# Top.net
KiCad netlist of a schematic drawn in Altium Designer
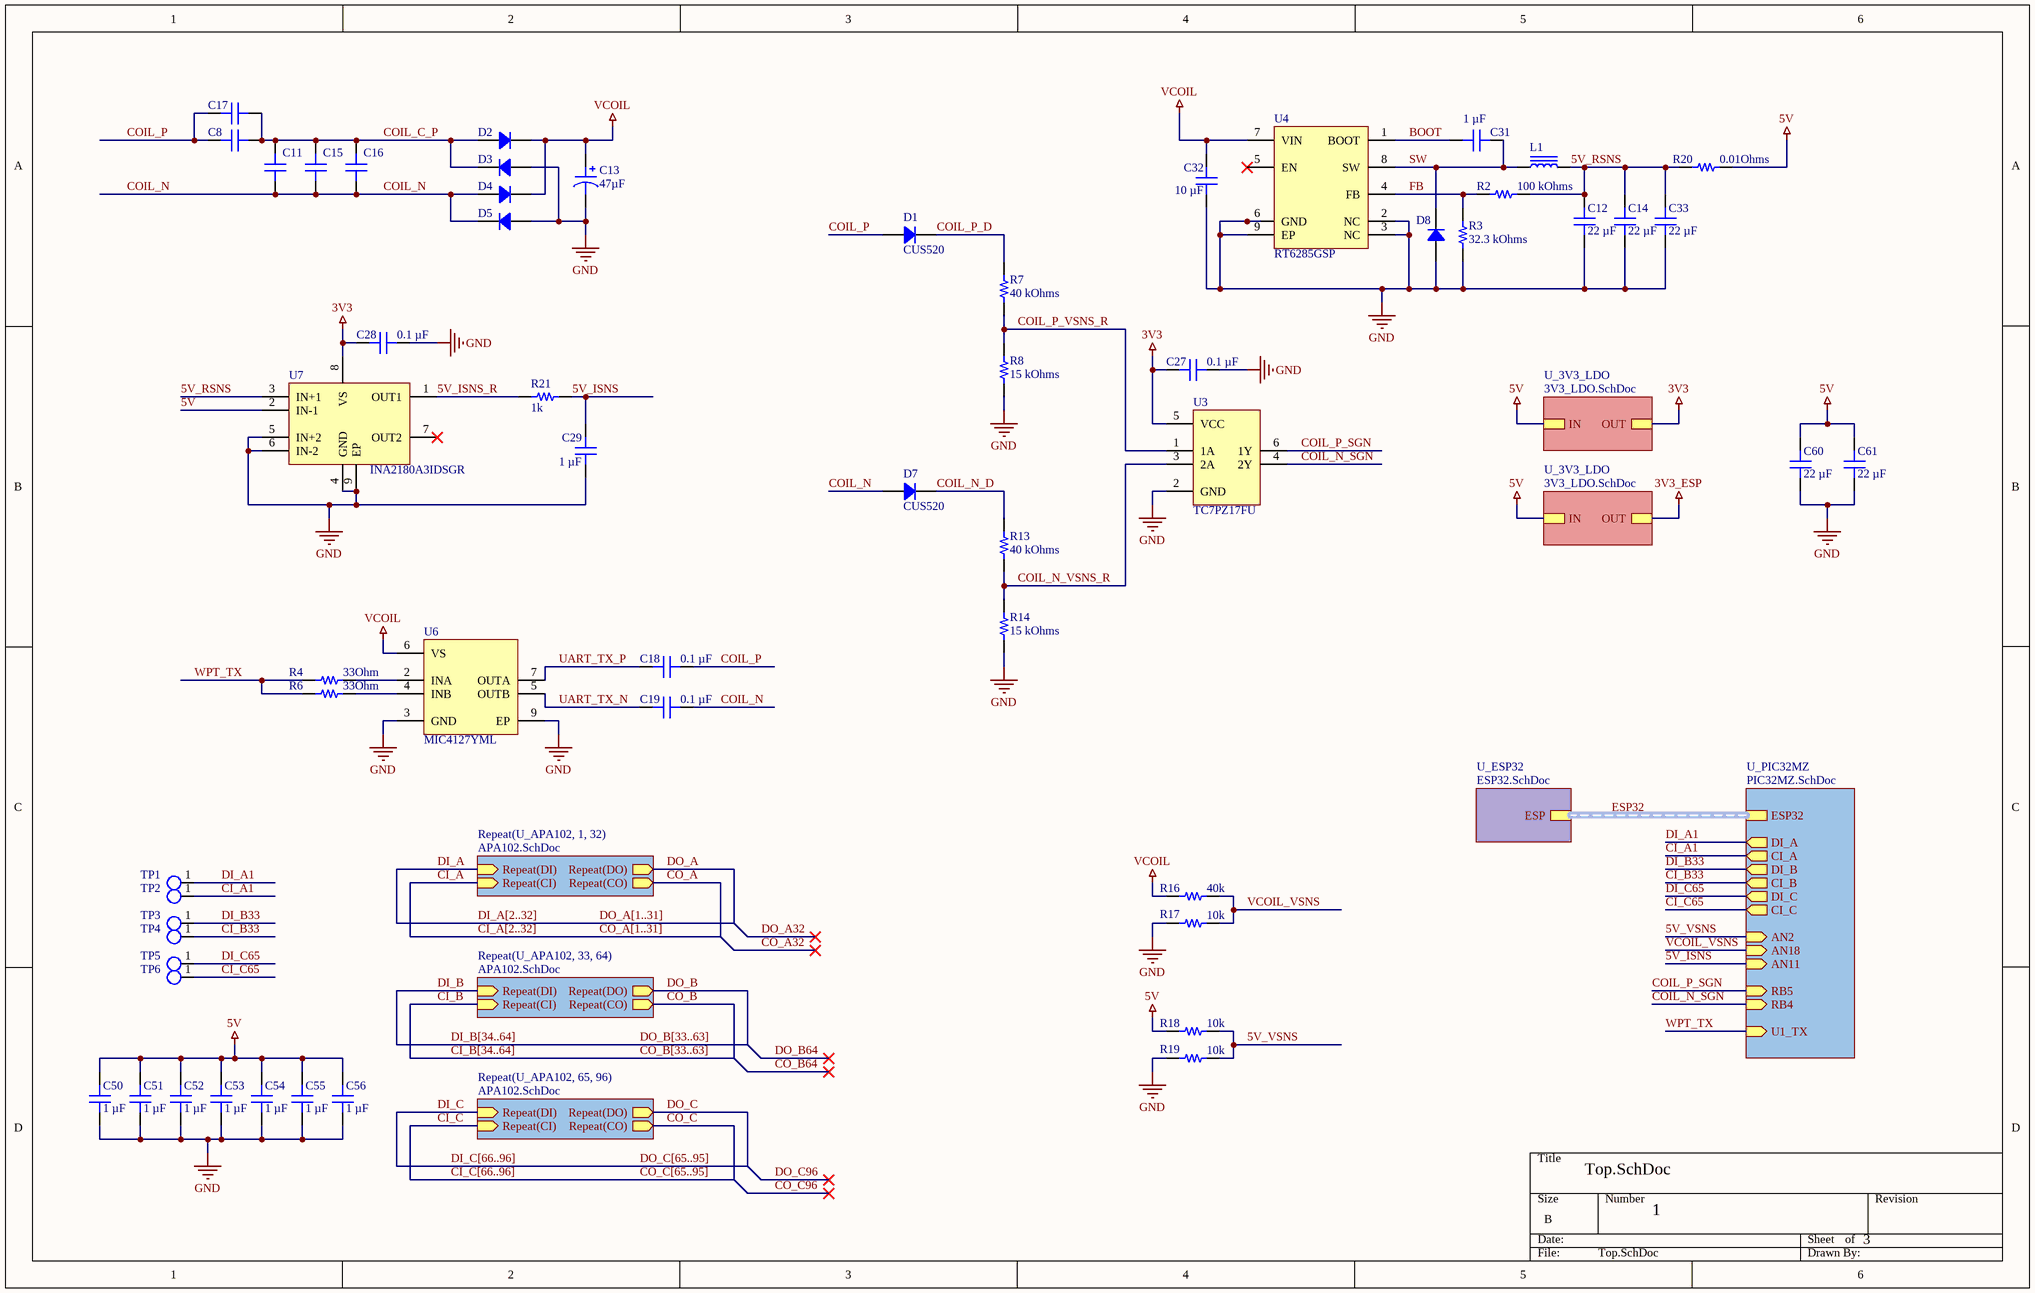
[diagram p0: Top.SchDoc]

(export (version "E")
  (design (tool "Eeschema 10.0.6"))
  (components
    (comp (ref "C8")
      (value "~")
      (footprint "CAP 1206_3216 - 0.8MM")
      (description "CAP CER 0.022UF 630V X7R 1206")
      (fields (field (name "PART NUMBER") "C1206C223KBRAC7800") (field (name "MANUFACTURER") "KEMET"))
      (libsource (lib "Celestial Altium Library - altium_library") (part "Capacitor"))
    )
    (comp (ref "C11")
      (value "~")
      (footprint "CAP 1206_3216 - 0.8MM")
      (description "CAP CER 0.022UF 630V X7R 1206")
      (fields (field (name "PART NUMBER") "C1206C223KBRAC7800") (field (name "MANUFACTURER") "KEMET"))
      (libsource (lib "Celestial Altium Library - altium_library") (part "Capacitor"))
    )
    (comp (ref "C12")
      (value "22 µF")
      (footprint "CAP 0603_1608")
      (description "CAP CER 22UF 10V X5R 0603")
      (fields (field (name "PART NUMBER") "0603ZD226MAT2A") (field (name "MANUFACTURER") "KYOCERA AVX"))
      (libsource (lib "Celestial Altium Library - altium_library") (part "Capacitor"))
    )
    (comp (ref "C13")
      (value "47µF")
      (footprint "CAP ALSMD 6.6MM H6.1MM")
      (description "ALUMINUM CAPACITOR")
      (fields
        (field (name "PART NUMBER") "EMHL160ARA470MF61G")
        (field (name "MANUFACTURER") "United Chemi-Con")
      )
      (libsource (lib "Celestial Altium Library - altium_library") (part "Polarised Capacitor"))
    )
    (comp (ref "C14")
      (value "22 µF")
      (footprint "CAP 0603_1608")
      (description "CAP CER 22UF 10V X5R 0603")
      (fields (field (name "PART NUMBER") "0603ZD226MAT2A") (field (name "MANUFACTURER") "KYOCERA AVX"))
      (libsource (lib "Celestial Altium Library - altium_library") (part "Capacitor"))
    )
    (comp (ref "C15")
      (value "~")
      (footprint "CAP 1206_3216 - 0.8MM")
      (description "CAP CER 0.022UF 630V X7R 1206")
      (fields (field (name "PART NUMBER") "C1206C223KBRAC7800") (field (name "MANUFACTURER") "KEMET"))
      (libsource (lib "Celestial Altium Library - altium_library") (part "Capacitor"))
    )
    (comp (ref "C16")
      (value "~")
      (footprint "CAP 1206_3216 - 0.8MM")
      (description "CAP CER 0.022UF 630V X7R 1206")
      (fields (field (name "PART NUMBER") "C1206C223KBRAC7800") (field (name "MANUFACTURER") "KEMET"))
      (libsource (lib "Celestial Altium Library - altium_library") (part "Capacitor"))
    )
    (comp (ref "C17")
      (value "~")
      (footprint "CAP 1206_3216 - 0.8MM")
      (description "CAP CER 0.022UF 630V X7R 1206")
      (fields (field (name "PART NUMBER") "C1206C223KBRAC7800") (field (name "MANUFACTURER") "KEMET"))
      (libsource (lib "Celestial Altium Library - altium_library") (part "Capacitor"))
    )
    (comp (ref "C18")
      (value "0.1 µF")
      (footprint "CAP 0402_1005")
      (description "CAP CER 0.1UF 25V X5R 0402")
      (fields
        (field (name "PART NUMBER") "C1005X5R1E104K050BC")
        (field (name "MANUFACTURER") "TDK Corporation")
      )
      (libsource (lib "Celestial Altium Library - altium_library") (part "Capacitor"))
    )
    (comp (ref "C19")
      (value "0.1 µF")
      (footprint "CAP 0402_1005")
      (description "CAP CER 0.1UF 25V X5R 0402")
      (fields
        (field (name "PART NUMBER") "C1005X5R1E104K050BC")
        (field (name "MANUFACTURER") "TDK Corporation")
      )
      (libsource (lib "Celestial Altium Library - altium_library") (part "Capacitor"))
    )
    (comp (ref "C27")
      (value "0.1 µF")
      (footprint "CAP 0402_1005")
      (description "CAP CER 0.1UF 25V X5R 0402")
      (fields
        (field (name "PART NUMBER") "C1005X5R1E104K050BC")
        (field (name "MANUFACTURER") "TDK Corporation")
      )
      (libsource (lib "Celestial Altium Library - altium_library") (part "Capacitor"))
    )
    (comp (ref "C28")
      (value "0.1 µF")
      (footprint "CAP 0402_1005")
      (description "CAP CER 0.1UF 25V X5R 0402")
      (fields
        (field (name "PART NUMBER") "C1005X5R1E104K050BC")
        (field (name "MANUFACTURER") "TDK Corporation")
      )
      (libsource (lib "Celestial Altium Library - altium_library") (part "Capacitor"))
    )
    (comp (ref "C29")
      (value "1 µF")
      (footprint "CAP 0402_1005")
      (description "CAP CER 0.1UF 25V X5R 0402")
      (fields
        (field (name "PART NUMBER") "C1005X5R1E104K050BC")
        (field (name "MANUFACTURER") "TDK Corporation")
      )
      (libsource (lib "Celestial Altium Library - altium_library") (part "Capacitor"))
    )
    (comp (ref "C31")
      (value "1 µF")
      (footprint "CAP 0402_1005")
      (description "CAP CER 0.1UF 25V X5R 0402")
      (fields
        (field (name "PART NUMBER") "C1005X5R1E104K050BC")
        (field (name "MANUFACTURER") "TDK Corporation")
      )
      (libsource (lib "Celestial Altium Library - altium_library") (part "Capacitor"))
    )
    (comp (ref "C32")
      (value "10 µF")
      (footprint "CAP 1210_3225 - 1MM")
      (description "CAP CER 10UF 50V X7R 1210")
      (fields
        (field (name "PART NUMBER") "C1210X106K050T")
        (field (name "MANUFACTURER") "Holy Stone Enterprise Co., Ltd.")
      )
      (libsource (lib "Celestial Altium Library - altium_library") (part "Capacitor"))
    )
    (comp (ref "C33")
      (value "22 µF")
      (footprint "CAP 0603_1608")
      (description "CAP CER 22UF 10V X5R 0603")
      (fields (field (name "PART NUMBER") "0603ZD226MAT2A") (field (name "MANUFACTURER") "KYOCERA AVX"))
      (libsource (lib "Celestial Altium Library - altium_library") (part "Capacitor"))
    )
    (comp (ref "C50")
      (value "1 µF")
      (footprint "CAP 0402_1005")
      (description "CAP CER 1UF 16V X5R 0402")
      (fields
        (field (name "PART NUMBER") "GRM155R61C105MA12D")
        (field (name "MANUFACTURER") "Murata Electronics")
      )
      (libsource (lib "Celestial Altium Library - altium_library") (part "Capacitor"))
    )
    (comp (ref "C51")
      (value "1 µF")
      (footprint "CAP 0402_1005")
      (description "CAP CER 1UF 16V X5R 0402")
      (fields
        (field (name "PART NUMBER") "GRM155R61C105MA12D")
        (field (name "MANUFACTURER") "Murata Electronics")
      )
      (libsource (lib "Celestial Altium Library - altium_library") (part "Capacitor"))
    )
    (comp (ref "C52")
      (value "1 µF")
      (footprint "CAP 0402_1005")
      (description "CAP CER 1UF 16V X5R 0402")
      (fields
        (field (name "PART NUMBER") "GRM155R61C105MA12D")
        (field (name "MANUFACTURER") "Murata Electronics")
      )
      (libsource (lib "Celestial Altium Library - altium_library") (part "Capacitor"))
    )
    (comp (ref "C53")
      (value "1 µF")
      (footprint "CAP 0402_1005")
      (description "CAP CER 1UF 16V X5R 0402")
      (fields
        (field (name "PART NUMBER") "GRM155R61C105MA12D")
        (field (name "MANUFACTURER") "Murata Electronics")
      )
      (libsource (lib "Celestial Altium Library - altium_library") (part "Capacitor"))
    )
    (comp (ref "C54")
      (value "1 µF")
      (footprint "CAP 0402_1005")
      (description "CAP CER 1UF 16V X5R 0402")
      (fields
        (field (name "PART NUMBER") "GRM155R61C105MA12D")
        (field (name "MANUFACTURER") "Murata Electronics")
      )
      (libsource (lib "Celestial Altium Library - altium_library") (part "Capacitor"))
    )
    (comp (ref "C55")
      (value "1 µF")
      (footprint "CAP 0402_1005")
      (description "CAP CER 1UF 16V X5R 0402")
      (fields
        (field (name "PART NUMBER") "GRM155R61C105MA12D")
        (field (name "MANUFACTURER") "Murata Electronics")
      )
      (libsource (lib "Celestial Altium Library - altium_library") (part "Capacitor"))
    )
    (comp (ref "C56")
      (value "1 µF")
      (footprint "CAP 0402_1005")
      (description "CAP CER 1UF 16V X5R 0402")
      (fields
        (field (name "PART NUMBER") "GRM155R61C105MA12D")
        (field (name "MANUFACTURER") "Murata Electronics")
      )
      (libsource (lib "Celestial Altium Library - altium_library") (part "Capacitor"))
    )
    (comp (ref "C60")
      (value "22 µF")
      (footprint "CAP 0603_1608")
      (description "CAP CER 22UF 10V X5R 0603")
      (fields (field (name "PART NUMBER") "0603ZD226MAT2A") (field (name "MANUFACTURER") "KYOCERA AVX"))
      (libsource (lib "Celestial Altium Library - altium_library") (part "Capacitor"))
    )
    (comp (ref "C61")
      (value "22 µF")
      (footprint "CAP 0603_1608")
      (description "CAP CER 22UF 10V X5R 0603")
      (fields (field (name "PART NUMBER") "0603ZD226MAT2A") (field (name "MANUFACTURER") "KYOCERA AVX"))
      (libsource (lib "Celestial Altium Library - altium_library") (part "Capacitor"))
    )
    (comp (ref "D1")
      (value "CUS520")
      (footprint "SOD323")
      (description "DIODE SCHOTTKY 30V 30MA SOD323")
      (fields (field (name "PART NUMBER") "NSVRB751V40T1G") (field (name "MANUFACTURER") "ON Semiconductor"))
      (libsource (lib "Celestial Altium Library - altium_library") (part "Diode"))
    )
    (comp (ref "D2")
      (value "STPS340UY")
      (footprint "DO214AA SMB")
      (description "DIODE SCHOTTKY 40V 3A SMB")
      (fields (field (name "MANUFACTURER") "STMicroelectronics"))
      (libsource (lib "Celestial Altium Library - altium_library") (part "Diode"))
    )
    (comp (ref "D3")
      (value "STPS340UY")
      (footprint "DO214AA SMB")
      (description "DIODE SCHOTTKY 40V 3A SMB")
      (fields (field (name "MANUFACTURER") "STMicroelectronics"))
      (libsource (lib "Celestial Altium Library - altium_library") (part "Diode"))
    )
    (comp (ref "D4")
      (value "STPS340UY")
      (footprint "DO214AA SMB")
      (description "DIODE SCHOTTKY 40V 3A SMB")
      (fields (field (name "MANUFACTURER") "STMicroelectronics"))
      (libsource (lib "Celestial Altium Library - altium_library") (part "Diode"))
    )
    (comp (ref "D5")
      (value "STPS340UY")
      (footprint "DO214AA SMB")
      (description "DIODE SCHOTTKY 40V 3A SMB")
      (fields (field (name "MANUFACTURER") "STMicroelectronics"))
      (libsource (lib "Celestial Altium Library - altium_library") (part "Diode"))
    )
    (comp (ref "D7")
      (value "CUS520")
      (footprint "SOD323")
      (description "DIODE SCHOTTKY 30V 30MA SOD323")
      (fields (field (name "PART NUMBER") "NSVRB751V40T1G") (field (name "MANUFACTURER") "ON Semiconductor"))
      (libsource (lib "Celestial Altium Library - altium_library") (part "Diode"))
    )
    (comp (ref "D8")
      (value "STPS340UY")
      (footprint "DO214AA SMB")
      (description "DIODE SCHOTTKY 40V 3A SMB")
      (fields (field (name "MANUFACTURER") "STMicroelectronics"))
      (libsource (lib "Celestial Altium Library - altium_library") (part "Diode"))
    )
    (comp (ref "L1")
      (value "MPL-AL5050-5R6")
      (footprint "MPL-AL5050-5R6")
      (description "FIXED IND 5.6UH 6.8A 20 MOHM SMD")
      (fields (field (name "MF") "Laird-Signal Integrity Products") (field (name "MP") "MGV05021R0M-10"))
      (libsource (lib "IC") (part "MPL-AL5050-5R6"))
    )
    (comp (ref "R2")
      (value "100 kOhms")
      (footprint "RES 0402_1005")
      (description "RES SMD 220K OHM 5% 1/5W 0402")
      (fields (field (name "PART NUMBER") "ESR01MZPJ224") (field (name "MANUFACTURER") "Rohm Semiconductor"))
      (libsource (lib "Celestial Altium Library - altium_library") (part "Resistor"))
    )
    (comp (ref "R3")
      (value "32.3 kOhms")
      (footprint "RES 0402_1005")
      (description "RES SMD 30K OHM 0.5% 1/16W 0402")
      (fields (field (name "PART NUMBER") "RT0402DRE0730KL") (field (name "MANUFACTURER") "Yageo"))
      (libsource (lib "Celestial Altium Library - altium_library") (part "Resistor"))
    )
    (comp (ref "R4")
      (value "33Ohm")
      (footprint "RES 0402_1005")
      (description "RES SMD 220K OHM 5% 1/5W 0402")
      (fields (field (name "PART NUMBER") "ESR01MZPJ224") (field (name "MANUFACTURER") "Rohm Semiconductor"))
      (libsource (lib "Celestial Altium Library - altium_library") (part "Resistor"))
    )
    (comp (ref "R6")
      (value "33Ohm")
      (footprint "RES 0402_1005")
      (description "RES SMD 220K OHM 5% 1/5W 0402")
      (fields (field (name "PART NUMBER") "ESR01MZPJ224") (field (name "MANUFACTURER") "Rohm Semiconductor"))
      (libsource (lib "Celestial Altium Library - altium_library") (part "Resistor"))
    )
    (comp (ref "R7")
      (value "40 kOhms")
      (footprint "RES 0402_1005")
      (description "RES SMD 30K OHM 0.5% 1/16W 0402")
      (fields (field (name "PART NUMBER") "RT0402DRE0730KL") (field (name "MANUFACTURER") "Yageo"))
      (libsource (lib "Celestial Altium Library - altium_library") (part "Resistor"))
    )
    (comp (ref "R8")
      (value "15 kOhms")
      (footprint "RES 0402_1005")
      (description "RES SMD 30K OHM 0.5% 1/16W 0402")
      (fields (field (name "PART NUMBER") "RT0402DRE0730KL") (field (name "MANUFACTURER") "Yageo"))
      (libsource (lib "Celestial Altium Library - altium_library") (part "Resistor"))
    )
    (comp (ref "R13")
      (value "40 kOhms")
      (footprint "RES 0402_1005")
      (description "RES SMD 30K OHM 0.5% 1/16W 0402")
      (fields (field (name "PART NUMBER") "RT0402DRE0730KL") (field (name "MANUFACTURER") "Yageo"))
      (libsource (lib "Celestial Altium Library - altium_library") (part "Resistor"))
    )
    (comp (ref "R14")
      (value "15 kOhms")
      (footprint "RES 0402_1005")
      (description "RES SMD 30K OHM 0.5% 1/16W 0402")
      (fields (field (name "PART NUMBER") "RT0402DRE0730KL") (field (name "MANUFACTURER") "Yageo"))
      (libsource (lib "Celestial Altium Library - altium_library") (part "Resistor"))
    )
    (comp (ref "R16")
      (value "40k")
      (footprint "RES 0402_1005")
      (description "RES SMD 30K OHM 0.5% 1/16W 0402")
      (fields (field (name "PART NUMBER") "RT0402DRE0730KL") (field (name "MANUFACTURER") "Yageo"))
      (libsource (lib "Celestial Altium Library - altium_library") (part "Resistor"))
    )
    (comp (ref "R17")
      (value "10k")
      (footprint "RES 0402_1005")
      (description "RES SMD 30K OHM 0.5% 1/16W 0402")
      (fields (field (name "PART NUMBER") "RT0402DRE0730KL") (field (name "MANUFACTURER") "Yageo"))
      (libsource (lib "Celestial Altium Library - altium_library") (part "Resistor"))
    )
    (comp (ref "R18")
      (value "10k")
      (footprint "RES 0402_1005")
      (description "RES SMD 30K OHM 0.5% 1/16W 0402")
      (fields (field (name "PART NUMBER") "RT0402DRE0730KL") (field (name "MANUFACTURER") "Yageo"))
      (libsource (lib "Celestial Altium Library - altium_library") (part "Resistor"))
    )
    (comp (ref "R19")
      (value "10k")
      (footprint "RES 0402_1005")
      (description "RES SMD 30K OHM 0.5% 1/16W 0402")
      (fields (field (name "PART NUMBER") "RT0402DRE0730KL") (field (name "MANUFACTURER") "Yageo"))
      (libsource (lib "Celestial Altium Library - altium_library") (part "Resistor"))
    )
    (comp (ref "R20")
      (value "0.01Ohms")
      (footprint "RES 0805_2012")
      (description "0805 CURRENT SENSING RES. 0.5%,")
      (fields
        (field (name "PART NUMBER") "ERJ-6CWDR027V")
        (field (name "MANUFACTURER") "Panasonic Electronic Components")
      )
      (libsource (lib "Celestial Altium Library - altium_library") (part "Resistor"))
    )
    (comp (ref "R21")
      (value "1k")
      (footprint "RES 0402_1005")
      (description "RES SMD 30K OHM 0.5% 1/16W 0402")
      (fields (field (name "PART NUMBER") "RT0402DRE0730KL") (field (name "MANUFACTURER") "Yageo"))
      (libsource (lib "Celestial Altium Library - altium_library") (part "Resistor"))
    )
    (comp (ref "TP1")
      (value "0.8mm")
      (footprint "TP  0.8mm")
      (description "Test point")
      (libsource (lib "IC") (part "TP 0.8mm"))
    )
    (comp (ref "TP2")
      (value "0.8mm")
      (footprint "TP  0.8mm")
      (description "Test point")
      (libsource (lib "IC") (part "TP 0.8mm"))
    )
    (comp (ref "TP3")
      (value "0.8mm")
      (footprint "TP  0.8mm")
      (description "Test point")
      (libsource (lib "IC") (part "TP 0.8mm"))
    )
    (comp (ref "TP4")
      (value "0.8mm")
      (footprint "TP  0.8mm")
      (description "Test point")
      (libsource (lib "IC") (part "TP 0.8mm"))
    )
    (comp (ref "TP5")
      (value "0.8mm")
      (footprint "TP  0.8mm")
      (description "Test point")
      (libsource (lib "IC") (part "TP 0.8mm"))
    )
    (comp (ref "TP6")
      (value "0.8mm")
      (footprint "TP  0.8mm")
      (description "Test point")
      (libsource (lib "IC") (part "TP 0.8mm"))
    )
    (comp (ref "U3")
      (value "TC7PZ17FU")
      (footprint "SOT-363")
      (description "2x Buffer")
      (libsource (lib "IC") (part "TC7PZ17FU"))
    )
    (comp (ref "U4")
      (value "RT6285GSP")
      (footprint "8-SOIC Richtek")
      (description "Buck, Adj, 5A")
      (libsource (lib "IC") (part "RT6285GSP"))
    )
    (comp (ref "U6")
      (value "MIC4127YML")
      (footprint "VDFN-8 3x3x0.9")
      (description "Low side Gate Driver 2x")
      (libsource (lib "IC") (part "MIC4127YML"))
    )
    (comp (ref "U7")
      (value "INA2180A3IDSGR")
      (footprint "SON50P200X200X80-9N")
      (description "Current sense amplifier 2 channel")
      (libsource (lib "IC") (part "INA2180"))
    )
  )
  (nets
    (net (code "188") (name "/5V_ISNS") (class "Default")
      (node (ref "C29") (pin "1") (pinfunction "1_1") (pintype "passive"))
      (node (ref "R21") (pin "1") (pinfunction "1_1") (pintype "passive"))
    )
    (net (code "189") (name "/5V_ISNS_R") (class "Default")
      (node (ref "R21") (pin "2") (pinfunction "2_2") (pintype "passive"))
      (node (ref "U7") (pin "1") (pinfunction "OUT1_1") (pintype "passive"))
    )
    (net (code "190") (name "/5V_RSNS") (class "Default")
      (node (ref "C12") (pin "2") (pinfunction "2_2") (pintype "passive"))
      (node (ref "C14") (pin "2") (pinfunction "2_2") (pintype "passive"))
      (node (ref "C33") (pin "2") (pinfunction "2_2") (pintype "passive"))
      (node (ref "L1") (pin "2") (pinfunction "2_2") (pintype "passive"))
      (node (ref "R2") (pin "2") (pinfunction "2_2") (pintype "passive"))
      (node (ref "R20") (pin "1") (pinfunction "1_1") (pintype "passive"))
      (node (ref "U7") (pin "3") (pinfunction "IN+1_3") (pintype "passive"))
    )
    (net (code "191") (name "/5V_VSNS") (class "Default")
      (node (ref "R18") (pin "1") (pinfunction "1_1") (pintype "passive"))
      (node (ref "R19") (pin "1") (pinfunction "1_1") (pintype "passive"))
    )
    (net (code "192") (name "/BOOT") (class "Default")
      (node (ref "C31") (pin "2") (pinfunction "2_2") (pintype "passive"))
      (node (ref "U4") (pin "1") (pinfunction "BOOT_1") (pintype "passive"))
    )
    (net (code "194") (name "/CI_A1") (class "Default")
      (node (ref "TP2") (pin "1") (pinfunction "TP_1") (pintype "passive"))
    )
    (net (code "197") (name "/CI_B33") (class "Default")
      (node (ref "TP4") (pin "1") (pinfunction "TP_1") (pintype "passive"))
    )
    (net (code "200") (name "/CI_C65") (class "Default")
      (node (ref "TP6") (pin "1") (pinfunction "TP_1") (pintype "passive"))
    )
    (net (code "202") (name "/COIL_C_P") (class "Default")
      (node (ref "C11") (pin "2") (pinfunction "2_2") (pintype "passive"))
      (node (ref "C15") (pin "2") (pinfunction "2_2") (pintype "passive"))
      (node (ref "C16") (pin "2") (pinfunction "2_2") (pintype "passive"))
      (node (ref "C17") (pin "1") (pinfunction "1_1") (pintype "passive"))
      (node (ref "C8") (pin "1") (pinfunction "1_1") (pintype "passive"))
      (node (ref "D2") (pin "1") (pinfunction "1_1") (pintype "passive"))
      (node (ref "D3") (pin "2") (pinfunction "2_2") (pintype "passive"))
    )
    (net (code "203") (name "/COIL_N") (class "Default")
      (node (ref "C11") (pin "1") (pinfunction "1_1") (pintype "passive"))
      (node (ref "C15") (pin "1") (pinfunction "1_1") (pintype "passive"))
      (node (ref "C16") (pin "1") (pinfunction "1_1") (pintype "passive"))
      (node (ref "C19") (pin "2") (pinfunction "2_2") (pintype "passive"))
      (node (ref "D4") (pin "1") (pinfunction "1_1") (pintype "passive"))
      (node (ref "D5") (pin "2") (pinfunction "2_2") (pintype "passive"))
      (node (ref "D7") (pin "1") (pinfunction "1_1") (pintype "passive"))
    )
    (net (code "204") (name "/COIL_N_D") (class "Default")
      (node (ref "D7") (pin "2") (pinfunction "2_2") (pintype "passive"))
      (node (ref "R13") (pin "2") (pinfunction "2_2") (pintype "passive"))
    )
    (net (code "205") (name "/COIL_N_SGN") (class "Default")
      (node (ref "U3") (pin "4") (pinfunction "2Y_4") (pintype "passive"))
    )
    (net (code "206") (name "/COIL_N_VSNS_R") (class "Default")
      (node (ref "R13") (pin "1") (pinfunction "1_1") (pintype "passive"))
      (node (ref "R14") (pin "2") (pinfunction "2_2") (pintype "passive"))
      (node (ref "U3") (pin "3") (pinfunction "2A_3") (pintype "passive"))
    )
    (net (code "207") (name "/COIL_P") (class "Default")
      (node (ref "C17") (pin "2") (pinfunction "2_2") (pintype "passive"))
      (node (ref "C18") (pin "2") (pinfunction "2_2") (pintype "passive"))
      (node (ref "C8") (pin "2") (pinfunction "2_2") (pintype "passive"))
      (node (ref "D1") (pin "1") (pinfunction "1_1") (pintype "passive"))
    )
    (net (code "208") (name "/COIL_P_D") (class "Default")
      (node (ref "D1") (pin "2") (pinfunction "2_2") (pintype "passive"))
      (node (ref "R7") (pin "2") (pinfunction "2_2") (pintype "passive"))
    )
    (net (code "209") (name "/COIL_P_SGN") (class "Default")
      (node (ref "U3") (pin "6") (pinfunction "1Y_6") (pintype "passive"))
    )
    (net (code "210") (name "/COIL_P_VSNS_R") (class "Default")
      (node (ref "R7") (pin "1") (pinfunction "1_1") (pintype "passive"))
      (node (ref "R8") (pin "2") (pinfunction "2_2") (pintype "passive"))
      (node (ref "U3") (pin "1") (pinfunction "1A_1") (pintype "passive"))
    )
    (net (code "218") (name "/DI_A1") (class "Default")
      (node (ref "TP1") (pin "1") (pinfunction "TP_1") (pintype "passive"))
    )
    (net (code "221") (name "/DI_B33") (class "Default")
      (node (ref "TP3") (pin "1") (pinfunction "TP_1") (pintype "passive"))
    )
    (net (code "224") (name "/DI_C65") (class "Default")
      (node (ref "TP5") (pin "1") (pinfunction "TP_1") (pintype "passive"))
    )
    (net (code "232") (name "/FB") (class "Default")
      (node (ref "R2") (pin "1") (pinfunction "1_1") (pintype "passive"))
      (node (ref "R3") (pin "2") (pinfunction "2_2") (pintype "passive"))
      (node (ref "U4") (pin "4") (pinfunction "FB_4") (pintype "passive"))
    )
    (net (code "233") (name "/SW") (class "Default")
      (node (ref "C31") (pin "1") (pinfunction "1_1") (pintype "passive"))
      (node (ref "D8") (pin "2") (pinfunction "2_2") (pintype "passive"))
      (node (ref "L1") (pin "1") (pinfunction "1_1") (pintype "passive"))
      (node (ref "U4") (pin "8") (pinfunction "SW_8") (pintype "passive"))
    )
    (net (code "234") (name "/UART_TX_N") (class "Default")
      (node (ref "C19") (pin "1") (pinfunction "1_1") (pintype "passive"))
      (node (ref "U6") (pin "5") (pinfunction "OUTB_5") (pintype "passive"))
    )
    (net (code "235") (name "/UART_TX_P") (class "Default")
      (node (ref "C18") (pin "1") (pinfunction "1_1") (pintype "passive"))
      (node (ref "U6") (pin "7") (pinfunction "OUTA_7") (pintype "passive"))
    )
    (net (code "236") (name "/VCOIL_VSNS") (class "Default")
      (node (ref "R16") (pin "1") (pinfunction "1_1") (pintype "passive"))
      (node (ref "R17") (pin "1") (pinfunction "1_1") (pintype "passive"))
    )
    (net (code "237") (name "/WPT_TX") (class "Default")
      (node (ref "R4") (pin "1") (pinfunction "1_1") (pintype "passive"))
      (node (ref "R6") (pin "1") (pinfunction "1_1") (pintype "passive"))
    )
    (net (code "239") (name "3V3") (class "Default")
      (node (ref "C27") (pin "2") (pinfunction "2_2") (pintype "passive"))
      (node (ref "C28") (pin "2") (pinfunction "2_2") (pintype "passive"))
      (node (ref "U3") (pin "5") (pinfunction "VCC_5") (pintype "passive"))
      (node (ref "U7") (pin "8") (pinfunction "VS_8") (pintype "passive"))
    )
    (net (code "241") (name "5V") (class "Default")
      (node (ref "C50") (pin "2") (pinfunction "2_2") (pintype "passive"))
      (node (ref "C51") (pin "2") (pinfunction "2_2") (pintype "passive"))
      (node (ref "C52") (pin "2") (pinfunction "2_2") (pintype "passive"))
      (node (ref "C53") (pin "2") (pinfunction "2_2") (pintype "passive"))
      (node (ref "C54") (pin "2") (pinfunction "2_2") (pintype "passive"))
      (node (ref "C55") (pin "2") (pinfunction "2_2") (pintype "passive"))
      (node (ref "C56") (pin "2") (pinfunction "2_2") (pintype "passive"))
      (node (ref "C60") (pin "2") (pinfunction "2_2") (pintype "passive"))
      (node (ref "C61") (pin "2") (pinfunction "2_2") (pintype "passive"))
      (node (ref "R18") (pin "2") (pinfunction "2_2") (pintype "passive"))
      (node (ref "R20") (pin "2") (pinfunction "2_2") (pintype "passive"))
      (node (ref "U7") (pin "2") (pinfunction "IN-1_2") (pintype "passive"))
    )
    (net (code "242") (name "GND") (class "Default")
      (node (ref "C12") (pin "1") (pinfunction "1_1") (pintype "passive"))
      (node (ref "C13") (pin "2") (pinfunction "2_2") (pintype "passive"))
      (node (ref "C14") (pin "1") (pinfunction "1_1") (pintype "passive"))
      (node (ref "C27") (pin "1") (pinfunction "1_1") (pintype "passive"))
      (node (ref "C28") (pin "1") (pinfunction "1_1") (pintype "passive"))
      (node (ref "C29") (pin "2") (pinfunction "2_2") (pintype "passive"))
      (node (ref "C32") (pin "1") (pinfunction "1_1") (pintype "passive"))
      (node (ref "C33") (pin "1") (pinfunction "1_1") (pintype "passive"))
      (node (ref "C50") (pin "1") (pinfunction "1_1") (pintype "passive"))
      (node (ref "C51") (pin "1") (pinfunction "1_1") (pintype "passive"))
      (node (ref "C52") (pin "1") (pinfunction "1_1") (pintype "passive"))
      (node (ref "C53") (pin "1") (pinfunction "1_1") (pintype "passive"))
      (node (ref "C54") (pin "1") (pinfunction "1_1") (pintype "passive"))
      (node (ref "C55") (pin "1") (pinfunction "1_1") (pintype "passive"))
      (node (ref "C56") (pin "1") (pinfunction "1_1") (pintype "passive"))
      (node (ref "C60") (pin "1") (pinfunction "1_1") (pintype "passive"))
      (node (ref "C61") (pin "1") (pinfunction "1_1") (pintype "passive"))
      (node (ref "D3") (pin "1") (pinfunction "1_1") (pintype "passive"))
      (node (ref "D5") (pin "1") (pinfunction "1_1") (pintype "passive"))
      (node (ref "D8") (pin "1") (pinfunction "1_1") (pintype "passive"))
      (node (ref "R14") (pin "1") (pinfunction "1_1") (pintype "passive"))
      (node (ref "R17") (pin "2") (pinfunction "2_2") (pintype "passive"))
      (node (ref "R19") (pin "2") (pinfunction "2_2") (pintype "passive"))
      (node (ref "R3") (pin "1") (pinfunction "1_1") (pintype "passive"))
      (node (ref "R8") (pin "1") (pinfunction "1_1") (pintype "passive"))
      (node (ref "U3") (pin "2") (pinfunction "GND_2") (pintype "passive"))
      (node (ref "U4") (pin "2") (pinfunction "NC_2") (pintype "passive"))
      (node (ref "U4") (pin "3") (pinfunction "NC_3") (pintype "passive"))
      (node (ref "U4") (pin "6") (pinfunction "GND_6") (pintype "passive"))
      (node (ref "U4") (pin "9") (pinfunction "EP_9") (pintype "passive"))
      (node (ref "U6") (pin "3") (pinfunction "GND_3") (pintype "passive"))
      (node (ref "U6") (pin "9") (pinfunction "EP_9") (pintype "passive"))
      (node (ref "U7") (pin "4") (pinfunction "GND_4") (pintype "passive"))
      (node (ref "U7") (pin "5") (pinfunction "IN+2_5") (pintype "passive"))
      (node (ref "U7") (pin "6") (pinfunction "IN-2_6") (pintype "passive"))
      (node (ref "U7") (pin "9") (pinfunction "EP_9") (pintype "passive"))
    )
    (net (code "243") (name "Net-(U6-INA)") (class "Default")
      (node (ref "R4") (pin "2") (pinfunction "2_2") (pintype "passive"))
      (node (ref "U6") (pin "2") (pinfunction "INA_2") (pintype "passive"))
    )
    (net (code "244") (name "Net-(U6-INB)") (class "Default")
      (node (ref "R6") (pin "2") (pinfunction "2_2") (pintype "passive"))
      (node (ref "U6") (pin "4") (pinfunction "INB_4") (pintype "passive"))
    )
    (net (code "245") (name "VCOIL") (class "Default")
      (node (ref "C13") (pin "1") (pinfunction "1_1") (pintype "passive"))
      (node (ref "C32") (pin "2") (pinfunction "2_2") (pintype "passive"))
      (node (ref "D2") (pin "2") (pinfunction "2_2") (pintype "passive"))
      (node (ref "D4") (pin "2") (pinfunction "2_2") (pintype "passive"))
      (node (ref "R16") (pin "2") (pinfunction "2_2") (pintype "passive"))
      (node (ref "U4") (pin "7") (pinfunction "VIN_7") (pintype "passive"))
      (node (ref "U6") (pin "6") (pinfunction "VS_6") (pintype "passive"))
    )
    (net (code "246") (name "unconnected-(U4-EN-Pad5)") (class "Default")
      (node (ref "U4") (pin "5") (pinfunction "EN_5") (pintype "passive+no_connect"))
    )
    (net (code "247") (name "unconnected-(U7-OUT2-Pad7)") (class "Default")
      (node (ref "U7") (pin "7") (pinfunction "OUT2_7") (pintype "passive+no_connect"))
    )
  )
)
